# Boost-to-12V-simplify_test.net
KiCad netlist of a schematic drawn in Altium Designer
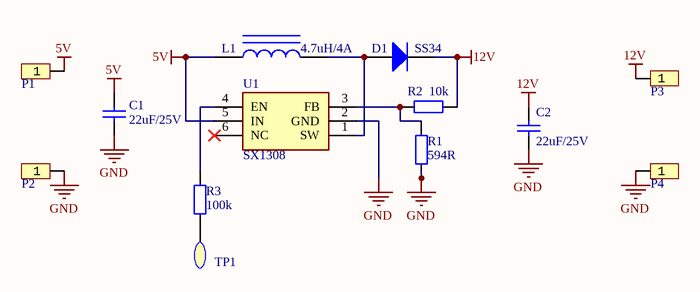
[diagram p0: Boost-to-12V-simplify_test.SchDoc]

(export (version "E")
  (design (tool "Eeschema 10.0.6"))
  (components
    (comp (ref "C1")
      (value "22uF/25V")
      (footprint "CAP-0603")
      (description "X7R")
      (libsource (lib "Power_Lib_Altium") (part "CAP"))
    )
    (comp (ref "C2")
      (value "22uF/25V")
      (footprint "CAP-0603")
      (description "X7R")
      (libsource (lib "Power_Lib_Altium") (part "CAP"))
    )
    (comp (ref "D1")
      (value "SS34")
      (footprint "DO-214AC_SMA")
      (description "肖特基二极管")
      (libsource (lib "Power_Lib_Altium") (part "DIODE"))
    )
    (comp (ref "L1")
      (value "4.7uH/4A")
      (footprint "SMD_7.3x7.3x4.2mm")
      (description "电感")
      (libsource (lib "Power_Lib_Altium") (part "INDUCTOR"))
    )
    (comp (ref "P1")
      (value "HDR1x2_2.54")
      (footprint "HDR1X1_2.54")
      (description "Header")
      (libsource (lib "Power_Lib_Altium") (part "HDR1x1_2.54"))
    )
    (comp (ref "P2")
      (value "HDR1x2_2.54")
      (footprint "HDR1X1_2.54")
      (description "Header")
      (libsource (lib "Power_Lib_Altium") (part "HDR1x1_2.54"))
    )
    (comp (ref "P3")
      (value "HDR1x2_2.54")
      (footprint "HDR1X1_2.54")
      (description "Header")
      (libsource (lib "") (part "HDR1x1_2.54_1"))
    )
    (comp (ref "P4")
      (value "HDR1x2_2.54")
      (footprint "HDR1X1_2.54")
      (description "Header")
      (libsource (lib "") (part "HDR1x1_2.54_1"))
    )
    (comp (ref "R1")
      (value "594R")
      (footprint "R-0603")
      (description "贴片电阻")
      (libsource (lib "Power_Lib_Altium") (part "RES"))
    )
    (comp (ref "R2")
      (value "10k")
      (footprint "R-0603")
      (description "贴片电阻")
      (libsource (lib "") (part "RES_1"))
    )
    (comp (ref "R3")
      (value "100k")
      (footprint "R-0603")
      (description "贴片电阻")
      (libsource (lib "Power_Lib_Altium") (part "RES"))
    )
    (comp (ref "TP1")
      (value "TestPoint")
      (footprint "TestPoint")
      (description "测试点")
      (libsource (lib "Power_Lib_Altium") (part "TestPoint"))
    )
    (comp (ref "U1")
      (value "SX1308")
      (footprint "SOT-23-6")
      (description "集成升压芯片")
      (libsource (lib "Power_Lib_Altium") (part "SX1308"))
    )
  )
  (nets
    (net (code "1") (name "5V") (class "Default")
      (node (ref "C1") (pin "2") (pinfunction "2_2") (pintype "passive"))
      (node (ref "L1") (pin "1") (pinfunction "1_1") (pintype "passive"))
      (node (ref "P1") (pin "1") (pinfunction "1_1") (pintype "passive"))
      (node (ref "U1") (pin "5") (pinfunction "IN_5") (pintype "passive"))
    )
    (net (code "2") (name "12V") (class "Default")
      (node (ref "C2") (pin "2") (pinfunction "2_2") (pintype "passive"))
      (node (ref "D1") (pin "2") (pinfunction "K_2") (pintype "passive"))
      (node (ref "P3") (pin "1") (pinfunction "1_1") (pintype "passive"))
      (node (ref "R2") (pin "2") (pinfunction "2_2") (pintype "passive"))
    )
    (net (code "3") (name "GND") (class "Default")
      (node (ref "C1") (pin "1") (pinfunction "1_1") (pintype "passive"))
      (node (ref "C2") (pin "1") (pinfunction "1_1") (pintype "passive"))
      (node (ref "P2") (pin "1") (pinfunction "1_1") (pintype "passive"))
      (node (ref "P4") (pin "1") (pinfunction "1_1") (pintype "passive"))
      (node (ref "R1") (pin "1") (pinfunction "1_1") (pintype "passive"))
      (node (ref "U1") (pin "2") (pinfunction "GND_2") (pintype "passive"))
    )
    (net (code "4") (name "Net-(D1-A)") (class "Default")
      (node (ref "D1") (pin "1") (pinfunction "A_1") (pintype "passive"))
      (node (ref "L1") (pin "2") (pinfunction "2_2") (pintype "passive"))
      (node (ref "U1") (pin "1") (pinfunction "SW_1") (pintype "passive"))
    )
    (net (code "5") (name "Net-(R3-Pad1)") (class "Default")
      (node (ref "R3") (pin "1") (pinfunction "1_1") (pintype "passive"))
      (node (ref "TP1") (pin "1") (pinfunction "1_1") (pintype "passive"))
    )
    (net (code "6") (name "Net-(U1-EN)") (class "Default")
      (node (ref "R3") (pin "2") (pinfunction "2_2") (pintype "passive"))
      (node (ref "U1") (pin "4") (pinfunction "EN_4") (pintype "passive"))
    )
    (net (code "7") (name "Net-(U1-FB)") (class "Default")
      (node (ref "R1") (pin "2") (pinfunction "2_2") (pintype "passive"))
      (node (ref "R2") (pin "1") (pinfunction "1_1") (pintype "passive"))
      (node (ref "U1") (pin "3") (pinfunction "FB_3") (pintype "passive"))
    )
    (net (code "8") (name "unconnected-(U1-NC-Pad6)") (class "Default")
      (node (ref "U1") (pin "6") (pinfunction "NC_6") (pintype "passive+no_connect"))
    )
  )
)
